# ct_back.net
KiCad netlist of a schematic drawn in Altium Designer
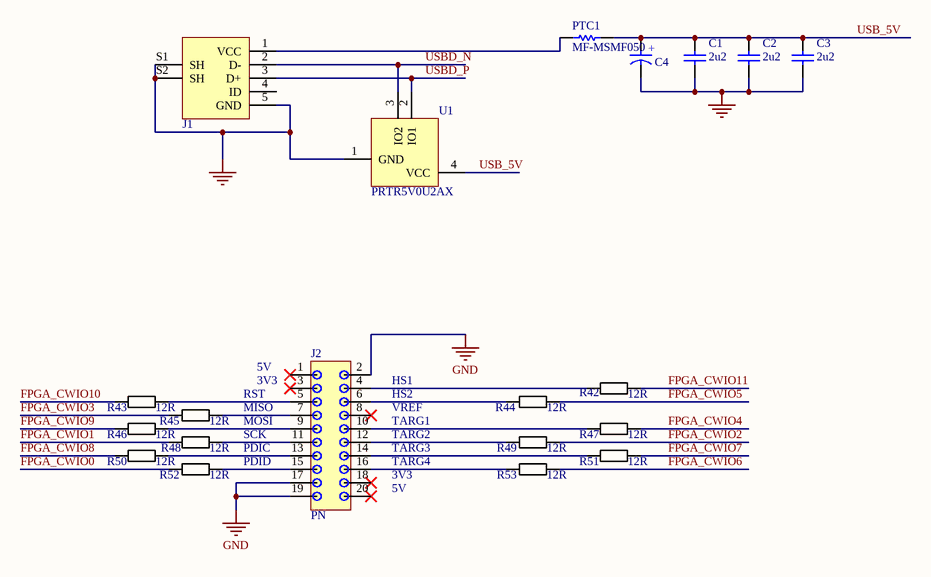
[diagram p0: ct_back.SchDoc]

(export (version "E")
  (design (tool "Eeschema 10.0.6"))
  (components
    (comp (ref "C1")
      (value "2u2")
      (footprint "CAPC0603_M")
      (description "2u2, 0603")
      (fields (field (name "PART NUMBER") "CCHIP-2u2-0603"))
      (libsource (lib "NewAE_AltiumLib") (part "CAP"))
    )
    (comp (ref "C2")
      (value "2u2")
      (footprint "CAPC0603_M")
      (description "2u2, 0603")
      (fields (field (name "PART NUMBER") "CCHIP-2u2-0603"))
      (libsource (lib "NewAE_AltiumLib") (part "CAP"))
    )
    (comp (ref "C3")
      (value "2u2")
      (footprint "CAPC0603_M")
      (description "2u2, 0603")
      (fields (field (name "PART NUMBER") "CCHIP-2u2-0603"))
      (libsource (lib "NewAE_AltiumLib") (part "CAP"))
    )
    (comp (ref "C4")
      (value "680uF")
      (footprint "Cap_16v_680uF")
      (description "Aluminum electrolytic 680uF, 8x16mm, radial")
      (fields (field (name "PART NUMBER") "Cap_16v_680uF"))
      (libsource (lib "NewAE_AltiumLib") (part "CAP_POL"))
    )
    (comp (ref "J1")
      (value "USB_MicroB_Jack")
      (footprint "ZX62D-B-5P8(30)")
      (description "CONN RCPT USB MICRO B SMD")
      (fields (field (name "PART NUMBER") "ZX62D-B-5P8(30)"))
      (libsource (lib "NewAE_AltiumLib") (part "USB_5PIN_2SHIELD"))
    )
    (comp (ref "J2")
      (value "PN")
      (footprint "CON-20HDR-EDGEMOUNT")
      (fields (field (name "PART NUMBER") "CON20HDR-EDGE"))
      (libsource (lib "NewAE_AltiumLib") (part "CON20_2ROW"))
    )
    (comp (ref "PTC1")
      (value "MF-MSMF050")
      (footprint "BOUR-MF-MSMF050-2_V")
      (description "MF-MSMF Series - PTC Resettable Fuse, 15 V Max, 0.15 Ohm Min, -40 to 85 degC, RoHS, Reel")
      (fields (field (name "MANUFACTURER") "Bourns"))
      (libsource (lib "Altium Content Vault") (part "CMP-0280-00002-2"))
    )
    (comp (ref "R42")
      (value "12R")
      (footprint "RESC1005X40N")
      (description "12R res, 0402, 1%, 1/16W")
      (fields (field (name "PART NUMBER") "RCHIP-12R-0402") (field (name "TOLERANCE") "1%"))
      (libsource (lib "NewAE_AltiumLib") (part "RES-EU"))
    )
    (comp (ref "R43")
      (value "12R")
      (footprint "RESC1005X40N")
      (description "12R res, 0402, 1%, 1/16W")
      (fields (field (name "PART NUMBER") "RCHIP-12R-0402") (field (name "TOLERANCE") "1%"))
      (libsource (lib "NewAE_AltiumLib") (part "RES-EU"))
    )
    (comp (ref "R44")
      (value "12R")
      (footprint "RESC1005X40N")
      (description "12R res, 0402, 1%, 1/16W")
      (fields (field (name "PART NUMBER") "RCHIP-12R-0402") (field (name "TOLERANCE") "1%"))
      (libsource (lib "NewAE_AltiumLib") (part "RES-EU"))
    )
    (comp (ref "R45")
      (value "12R")
      (footprint "RESC1005X40N")
      (description "12R res, 0402, 1%, 1/16W")
      (fields (field (name "PART NUMBER") "RCHIP-12R-0402") (field (name "TOLERANCE") "1%"))
      (libsource (lib "NewAE_AltiumLib") (part "RES-EU"))
    )
    (comp (ref "R46")
      (value "12R")
      (footprint "RESC1005X40N")
      (description "12R res, 0402, 1%, 1/16W")
      (fields (field (name "PART NUMBER") "RCHIP-12R-0402") (field (name "TOLERANCE") "1%"))
      (libsource (lib "NewAE_AltiumLib") (part "RES-EU"))
    )
    (comp (ref "R47")
      (value "12R")
      (footprint "RESC1005X40N")
      (description "12R res, 0402, 1%, 1/16W")
      (fields (field (name "PART NUMBER") "RCHIP-12R-0402") (field (name "TOLERANCE") "1%"))
      (libsource (lib "NewAE_AltiumLib") (part "RES-EU"))
    )
    (comp (ref "R48")
      (value "12R")
      (footprint "RESC1005X40N")
      (description "12R res, 0402, 1%, 1/16W")
      (fields (field (name "PART NUMBER") "RCHIP-12R-0402") (field (name "TOLERANCE") "1%"))
      (libsource (lib "NewAE_AltiumLib") (part "RES-EU"))
    )
    (comp (ref "R49")
      (value "12R")
      (footprint "RESC1005X40N")
      (description "12R res, 0402, 1%, 1/16W")
      (fields (field (name "PART NUMBER") "RCHIP-12R-0402") (field (name "TOLERANCE") "1%"))
      (libsource (lib "NewAE_AltiumLib") (part "RES-EU"))
    )
    (comp (ref "R50")
      (value "12R")
      (footprint "RESC1005X40N")
      (description "12R res, 0402, 1%, 1/16W")
      (fields (field (name "PART NUMBER") "RCHIP-12R-0402") (field (name "TOLERANCE") "1%"))
      (libsource (lib "NewAE_AltiumLib") (part "RES-EU"))
    )
    (comp (ref "R51")
      (value "12R")
      (footprint "RESC1005X40N")
      (description "12R res, 0402, 1%, 1/16W")
      (fields (field (name "PART NUMBER") "RCHIP-12R-0402") (field (name "TOLERANCE") "1%"))
      (libsource (lib "NewAE_AltiumLib") (part "RES-EU"))
    )
    (comp (ref "R52")
      (value "12R")
      (footprint "RESC1005X40N")
      (description "12R res, 0402, 1%, 1/16W")
      (fields (field (name "PART NUMBER") "RCHIP-12R-0402") (field (name "TOLERANCE") "1%"))
      (libsource (lib "NewAE_AltiumLib") (part "RES-EU"))
    )
    (comp (ref "R53")
      (value "12R")
      (footprint "RESC1005X40N")
      (description "12R res, 0402, 1%, 1/16W")
      (fields (field (name "PART NUMBER") "RCHIP-12R-0402") (field (name "TOLERANCE") "1%"))
      (libsource (lib "NewAE_AltiumLib") (part "RES-EU"))
    )
    (comp (ref "U1")
      (value "PRTR5V0U2AX")
      (footprint "SOT143B")
      (description "USB 2.0 high-speed ESD")
      (libsource (lib "NewAE_AltiumLib") (part "PRTR5V0U2AX"))
    )
  )
  (nets
    (net (code "1") (name "/FPGA_CWIO0") (class "Default")
      (node (ref "R52") (pin "1") (pinfunction "1_1") (pintype "passive"))
    )
    (net (code "2") (name "/FPGA_CWIO1") (class "Default")
      (node (ref "R48") (pin "1") (pinfunction "1_1") (pintype "passive"))
    )
    (net (code "3") (name "/FPGA_CWIO2") (class "Default")
      (node (ref "R49") (pin "2") (pinfunction "2_2") (pintype "passive"))
    )
    (net (code "4") (name "/FPGA_CWIO3") (class "Default")
      (node (ref "R45") (pin "1") (pinfunction "1_1") (pintype "passive"))
    )
    (net (code "5") (name "/FPGA_CWIO4") (class "Default")
      (node (ref "R47") (pin "2") (pinfunction "2_2") (pintype "passive"))
    )
    (net (code "6") (name "/FPGA_CWIO5") (class "Default")
      (node (ref "R44") (pin "2") (pinfunction "2_2") (pintype "passive"))
    )
    (net (code "7") (name "/FPGA_CWIO6") (class "Default")
      (node (ref "R53") (pin "2") (pinfunction "2_2") (pintype "passive"))
    )
    (net (code "8") (name "/FPGA_CWIO7") (class "Default")
      (node (ref "R51") (pin "2") (pinfunction "2_2") (pintype "passive"))
    )
    (net (code "9") (name "/FPGA_CWIO8") (class "Default")
      (node (ref "R50") (pin "1") (pinfunction "1_1") (pintype "passive"))
    )
    (net (code "10") (name "/FPGA_CWIO9") (class "Default")
      (node (ref "R46") (pin "1") (pinfunction "1_1") (pintype "passive"))
    )
    (net (code "11") (name "/FPGA_CWIO10") (class "Default")
      (node (ref "R43") (pin "1") (pinfunction "1_1") (pintype "passive"))
    )
    (net (code "12") (name "/FPGA_CWIO11") (class "Default")
      (node (ref "R42") (pin "2") (pinfunction "2_2") (pintype "passive"))
    )
    (net (code "13") (name "/USBD_N") (class "Default")
      (node (ref "J1") (pin "2") (pinfunction "D-_2") (pintype "passive"))
      (node (ref "U1") (pin "3") (pinfunction "IO2_3") (pintype "passive"))
    )
    (net (code "14") (name "/USBD_P") (class "Default")
      (node (ref "J1") (pin "3") (pinfunction "D+_3") (pintype "passive"))
      (node (ref "U1") (pin "2") (pinfunction "IO1_2") (pintype "passive"))
    )
    (net (code "15") (name "/USB_5V") (class "Default")
      (node (ref "C1") (pin "1") (pinfunction "1_1") (pintype "passive"))
      (node (ref "C2") (pin "1") (pinfunction "1_1") (pintype "passive"))
      (node (ref "C3") (pin "1") (pinfunction "1_1") (pintype "passive"))
      (node (ref "C4") (pin "1") (pinfunction "1_1") (pintype "passive"))
      (node (ref "PTC1") (pin "2") (pinfunction "2_2") (pintype "passive"))
      (node (ref "U1") (pin "4") (pinfunction "VCC_4") (pintype "power_in"))
    )
    (net (code "16") (name "GND") (class "Default")
      (node (ref "C1") (pin "2") (pinfunction "2_2") (pintype "passive"))
      (node (ref "C2") (pin "2") (pinfunction "2_2") (pintype "passive"))
      (node (ref "C3") (pin "2") (pinfunction "2_2") (pintype "passive"))
      (node (ref "C4") (pin "2") (pinfunction "2_2") (pintype "passive"))
      (node (ref "J1") (pin "5") (pinfunction "GND_5") (pintype "power_in"))
      (node (ref "J1") (pin "S1") (pinfunction "SH_S1") (pintype "passive"))
      (node (ref "J1") (pin "S2") (pinfunction "SH_S2") (pintype "passive"))
      (node (ref "J2") (pin "17") (pinfunction "9_17") (pintype "passive"))
      (node (ref "J2") (pin "19") (pinfunction "9_19") (pintype "passive"))
      (node (ref "J2") (pin "2") (pinfunction "2_2") (pintype "passive"))
      (node (ref "U1") (pin "1") (pinfunction "GND_1") (pintype "power_in"))
    )
    (net (code "17") (name "Net-(J1-VCC)") (class "Default")
      (node (ref "J1") (pin "1") (pinfunction "VCC_1") (pintype "passive"))
      (node (ref "PTC1") (pin "1") (pinfunction "1_1") (pintype "passive"))
    )
    (net (code "18") (name "Net-(J2-9-Pad11)") (class "Default")
      (node (ref "J2") (pin "11") (pinfunction "9_11") (pintype "passive"))
      (node (ref "R48") (pin "2") (pinfunction "2_2") (pintype "passive"))
    )
    (net (code "19") (name "Net-(J2-9-Pad13)") (class "Default")
      (node (ref "J2") (pin "13") (pinfunction "9_13") (pintype "passive"))
      (node (ref "R50") (pin "2") (pinfunction "2_2") (pintype "passive"))
    )
    (net (code "20") (name "Net-(J2-9-Pad15)") (class "Default")
      (node (ref "J2") (pin "15") (pinfunction "9_15") (pintype "passive"))
      (node (ref "R52") (pin "2") (pinfunction "2_2") (pintype "passive"))
    )
    (net (code "21") (name "Net-(J2-10-Pad12)") (class "Default")
      (node (ref "J2") (pin "12") (pinfunction "10_12") (pintype "passive"))
      (node (ref "R49") (pin "1") (pinfunction "1_1") (pintype "passive"))
    )
    (net (code "22") (name "Net-(J2-10-Pad14)") (class "Default")
      (node (ref "J2") (pin "14") (pinfunction "10_14") (pintype "passive"))
      (node (ref "R51") (pin "1") (pinfunction "1_1") (pintype "passive"))
    )
    (net (code "23") (name "Net-(J2-10-Pad16)") (class "Default")
      (node (ref "J2") (pin "16") (pinfunction "10_16") (pintype "passive"))
      (node (ref "R53") (pin "1") (pinfunction "1_1") (pintype "passive"))
    )
    (net (code "24") (name "Net-(J2-Pad4)") (class "Default")
      (node (ref "J2") (pin "4") (pinfunction "4_4") (pintype "passive"))
      (node (ref "R42") (pin "1") (pinfunction "1_1") (pintype "passive"))
    )
    (net (code "25") (name "Net-(J2-Pad5)") (class "Default")
      (node (ref "J2") (pin "5") (pinfunction "5_5") (pintype "passive"))
      (node (ref "R43") (pin "2") (pinfunction "2_2") (pintype "passive"))
    )
    (net (code "26") (name "Net-(J2-Pad6)") (class "Default")
      (node (ref "J2") (pin "6") (pinfunction "6_6") (pintype "passive"))
      (node (ref "R44") (pin "1") (pinfunction "1_1") (pintype "passive"))
    )
    (net (code "27") (name "Net-(J2-Pad7)") (class "Default")
      (node (ref "J2") (pin "7") (pinfunction "7_7") (pintype "passive"))
      (node (ref "R45") (pin "2") (pinfunction "2_2") (pintype "passive"))
    )
    (net (code "28") (name "Net-(J2-Pad9)") (class "Default")
      (node (ref "J2") (pin "9") (pinfunction "9_9") (pintype "passive"))
      (node (ref "R46") (pin "2") (pinfunction "2_2") (pintype "passive"))
    )
    (net (code "29") (name "Net-(J2-Pad10)") (class "Default")
      (node (ref "J2") (pin "10") (pinfunction "10_10") (pintype "passive"))
      (node (ref "R47") (pin "1") (pinfunction "1_1") (pintype "passive"))
    )
    (net (code "30") (name "unconnected-(J1-ID-Pad4)") (class "Default")
      (node (ref "J1") (pin "4") (pinfunction "ID_4") (pintype "power_in"))
    )
    (net (code "31") (name "unconnected-(J2-10-Pad18)") (class "Default")
      (node (ref "J2") (pin "18") (pinfunction "10_18") (pintype "passive+no_connect"))
    )
    (net (code "32") (name "unconnected-(J2-10-Pad20)") (class "Default")
      (node (ref "J2") (pin "20") (pinfunction "10_20") (pintype "passive+no_connect"))
    )
    (net (code "33") (name "unconnected-(J2-Pad1)") (class "Default")
      (node (ref "J2") (pin "1") (pinfunction "1_1") (pintype "passive+no_connect"))
    )
    (net (code "34") (name "unconnected-(J2-Pad3)") (class "Default")
      (node (ref "J2") (pin "3") (pinfunction "3_3") (pintype "passive+no_connect"))
    )
    (net (code "35") (name "unconnected-(J2-Pad8)") (class "Default")
      (node (ref "J2") (pin "8") (pinfunction "8_8") (pintype "passive+no_connect"))
    )
  )
)
